# AD5324_Digital-to-Analog_Converter.net
KiCad netlist of a schematic drawn in Altium Designer
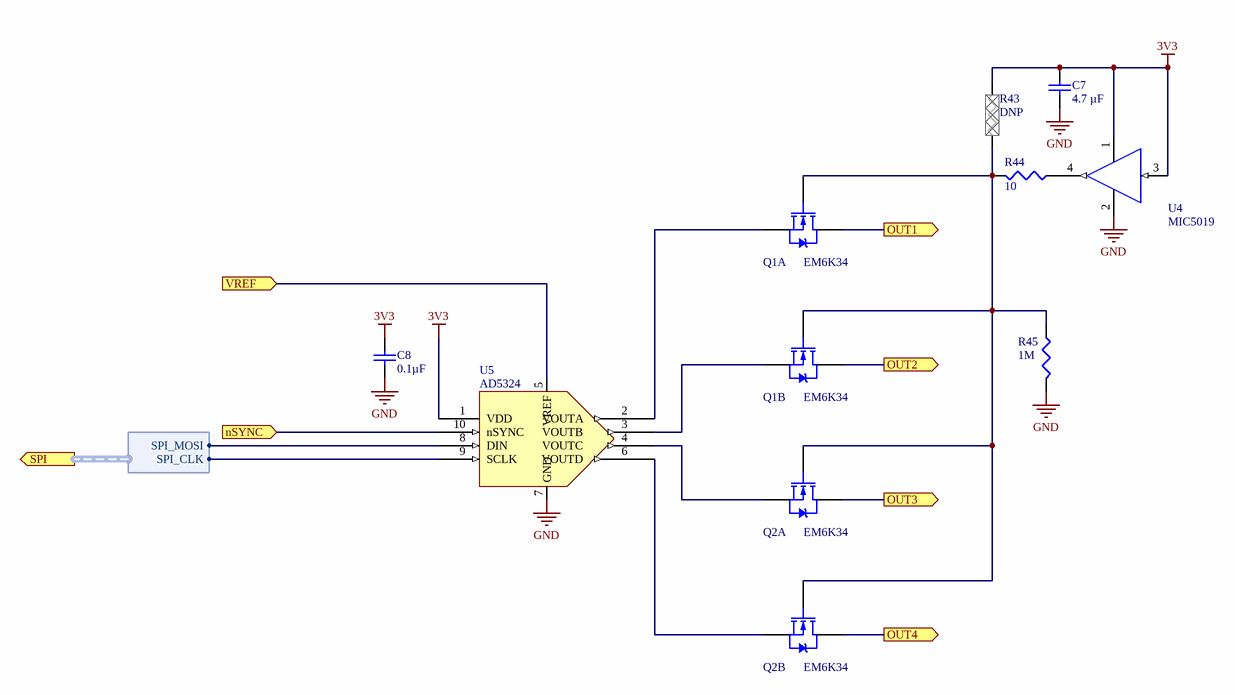
[diagram p0: AD5324 Digital-to-Analog Converter.SchDoc]

(export (version "E")
  (design (tool "Eeschema 10.0.6"))
  (components
    (comp (ref "C7")
      (value "4.7 µF")
      (footprint "MUR-GRM188")
      (description "CAP CER 4.7UF 16V X7R 0603")
      (fields
        (field (name "PART NUMBER") "10165")
        (field (name "MANUFACTURER PART NUMBER") "GRM188Z71C475KE21D")
        (field (name "PUBLISHER") "Altium Limited")
      )
      (libsource (lib "Database") (part "Cap"))
    )
    (comp (ref "C8")
      (value "0.1µF")
      (footprint "TDK-CGA2B")
      (description "CAP CER 0.1UF 50V X7R 0402")
      (fields
        (field (name "PART NUMBER") "PC-TDK-02259")
        (field (name "MANUFACTURER PART NUMBER") "CGA2B3X7R1H104K050BB")
        (field (name "PUBLISHER") "AlbertaSat")
      )
      (libsource (lib "Database") (part "Cap"))
    )
    (comp (ref "Q1")
      (value "EM6K34")
      (footprint "ROH-EMT6")
      (description "MOSFET 2N-CH 50V 0.2A EMT6")
      (fields
        (field (name "PART NUMBER") "PQ-ROH-00008")
        (field (name "MANUFACTURER PART NUMBER") "EM6K34T2CR")
        (field (name "PUBLISHER") "AlbertaSat")
      )
      (libsource (lib "Database") (part "EM6K34T2CR"))
    )
    (comp (ref "Q2")
      (value "EM6K34")
      (footprint "ROH-EMT6")
      (description "MOSFET 2N-CH 50V 0.2A EMT6")
      (fields
        (field (name "PART NUMBER") "PQ-ROH-00008")
        (field (name "MANUFACTURER PART NUMBER") "EM6K34T2CR")
        (field (name "PUBLISHER") "AlbertaSat")
      )
      (libsource (lib "Database") (part "EM6K34T2CR"))
    )
    (comp (ref "R43")
      (value "DNP")
      (footprint "PANA-ERA2A")
      (fields (field (name "PART NUMBER") "19768"))
      (libsource (lib "Database") (part "DNPRes"))
    )
    (comp (ref "R44")
      (value "10")
      (footprint "PANA-ERA2A")
      (description "RES SMD 10 OHM 0.5% 1/16W 0402")
      (fields
        (field (name "PART NUMBER") "13235")
        (field (name "MANUFACTURER PART NUMBER") "ERA-2AKD100X")
        (field (name "PUBLISHER") "Altium Limited")
      )
      (libsource (lib "Database") (part "Res3"))
    )
    (comp (ref "R45")
      (value "1M")
      (footprint "PANA-ERJ2R")
      (description "RES SMD 1M OHM 1% 1/10W 0402")
      (fields
        (field (name "PART NUMBER") "19704")
        (field (name "MANUFACTURER PART NUMBER") "ERJ-2RKF1004X")
        (field (name "PUBLISHER") "Altium Limited")
      )
      (libsource (lib "Database") (part "Res3"))
    )
    (comp (ref "U4")
      (value "MIC5019")
      (footprint "MCP-MIC5019")
      (description "IC GATE DRVR HIGH-SIDE 4TQFN")
      (fields
        (field (name "PART NUMBER") "PU-MCP-00008")
        (field (name "MANUFACTURER PART NUMBER") "MIC5019YFT-TR")
        (field (name "PUBLISHER") "AlbertaSat")
      )
      (libsource (lib "Database") (part "MIC5019YFT-TR"))
    )
    (comp (ref "U5")
      (value "AD5324")
      (footprint "ADI-RM-10")
      (description "IC DAC 12BIT V-OUT 10MSOP")
      (fields
        (field (name "PART NUMBER") "PU-ADI-00016")
        (field (name "MANUFACTURER PART NUMBER") "AD5324BRMZ")
        (field (name "PUBLISHER") "AlbertaSat")
      )
      (libsource (lib "Database") (part "AD5324BRMZ"))
    )
  )
  (nets
    (net (code "2") (name "/OUT1") (class "Default")
      (node (ref "Q1") (pin "6") (pinfunction "D1_6") (pintype "passive"))
    )
    (net (code "3") (name "/OUT2") (class "Default")
      (node (ref "Q1") (pin "3") (pinfunction "D2_3") (pintype "passive"))
    )
    (net (code "4") (name "/OUT3") (class "Default")
      (node (ref "Q2") (pin "6") (pinfunction "D1_6") (pintype "passive"))
    )
    (net (code "5") (name "/OUT4") (class "Default")
      (node (ref "Q2") (pin "3") (pinfunction "D2_3") (pintype "passive"))
    )
    (net (code "6") (name "/SPI_CLK") (class "Default")
      (node (ref "U5") (pin "9") (pinfunction "SCLK_9") (pintype "input"))
    )
    (net (code "7") (name "/SPI_MOSI") (class "Default")
      (node (ref "U5") (pin "8") (pinfunction "DIN_8") (pintype "input"))
    )
    (net (code "8") (name "/VREF") (class "Default")
      (node (ref "U5") (pin "5") (pinfunction "VREF_5") (pintype "power_in"))
    )
    (net (code "9") (name "/nSYNC") (class "Default")
      (node (ref "U5") (pin "10") (pinfunction "nSYNC_10") (pintype "input"))
    )
    (net (code "11") (name "3V3") (class "Default")
      (node (ref "C7") (pin "2") (pinfunction "2_2") (pintype "passive"))
      (node (ref "C8") (pin "1") (pinfunction "1_1") (pintype "passive"))
      (node (ref "R43") (pin "2") (pinfunction "2_2") (pintype "passive"))
      (node (ref "U4") (pin "1") (pinfunction "VDD_1") (pintype "power_in"))
      (node (ref "U4") (pin "3") (pinfunction "IN_3") (pintype "input"))
      (node (ref "U5") (pin "1") (pinfunction "VDD_1") (pintype "power_in"))
    )
    (net (code "12") (name "GND") (class "Default")
      (node (ref "C7") (pin "1") (pinfunction "1_1") (pintype "passive"))
      (node (ref "C8") (pin "2") (pinfunction "2_2") (pintype "passive"))
      (node (ref "R45") (pin "1") (pinfunction "1_1") (pintype "passive"))
      (node (ref "U4") (pin "2") (pinfunction "GND_2") (pintype "power_in"))
      (node (ref "U5") (pin "7") (pinfunction "GND_7") (pintype "power_in"))
    )
    (net (code "13") (name "Net-(Q1A-G1)") (class "Default")
      (node (ref "Q1") (pin "1") (pinfunction "G1_1") (pintype "passive"))
      (node (ref "Q1") (pin "4") (pinfunction "G2_4") (pintype "passive"))
      (node (ref "Q2") (pin "1") (pinfunction "G1_1") (pintype "passive"))
      (node (ref "Q2") (pin "4") (pinfunction "G2_4") (pintype "passive"))
      (node (ref "R43") (pin "1") (pinfunction "1_1") (pintype "passive"))
      (node (ref "R44") (pin "2") (pinfunction "2_2") (pintype "passive"))
      (node (ref "R45") (pin "2") (pinfunction "2_2") (pintype "passive"))
    )
    (net (code "14") (name "Net-(Q1A-S1)") (class "Default")
      (node (ref "Q1") (pin "2") (pinfunction "S1_2") (pintype "passive"))
      (node (ref "U5") (pin "2") (pinfunction "VOUTA_2") (pintype "output"))
    )
    (net (code "15") (name "Net-(Q1B-S2)") (class "Default")
      (node (ref "Q1") (pin "5") (pinfunction "S2_5") (pintype "passive"))
      (node (ref "U5") (pin "3") (pinfunction "VOUTB_3") (pintype "output"))
    )
    (net (code "16") (name "Net-(Q2A-S1)") (class "Default")
      (node (ref "Q2") (pin "2") (pinfunction "S1_2") (pintype "passive"))
      (node (ref "U5") (pin "4") (pinfunction "VOUTC_4") (pintype "output"))
    )
    (net (code "17") (name "Net-(Q2B-S2)") (class "Default")
      (node (ref "Q2") (pin "5") (pinfunction "S2_5") (pintype "passive"))
      (node (ref "U5") (pin "6") (pinfunction "VOUTD_6") (pintype "output"))
    )
    (net (code "18") (name "Net-(U4-OUT)") (class "Default")
      (node (ref "R44") (pin "1") (pinfunction "1_1") (pintype "passive"))
      (node (ref "U4") (pin "4") (pinfunction "OUT_4") (pintype "output"))
    )
  )
)
